# ProtonOnAStick.net
KiCad netlist of a schematic drawn in EAGLE
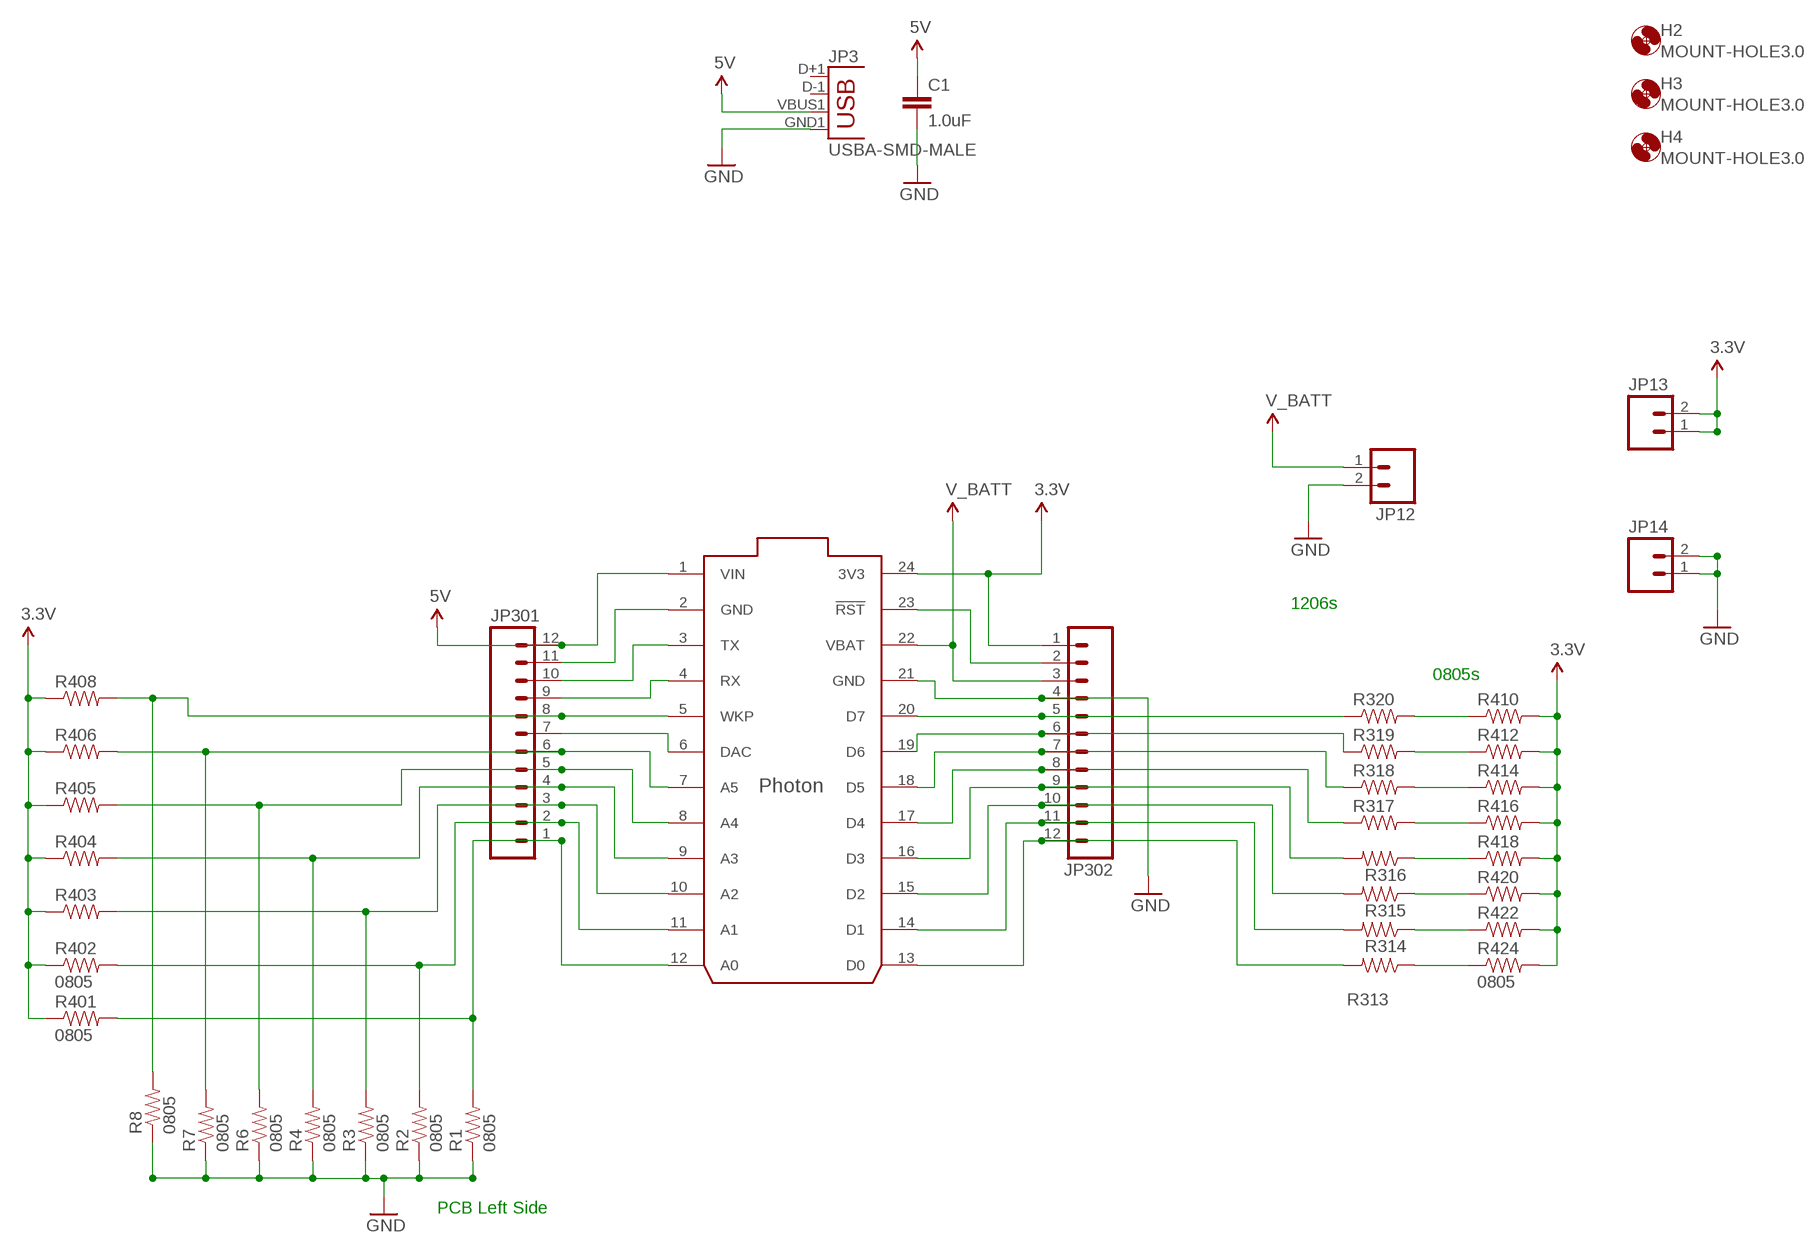
[diagram p0: schematic, sheet 1, part 1 of 2]
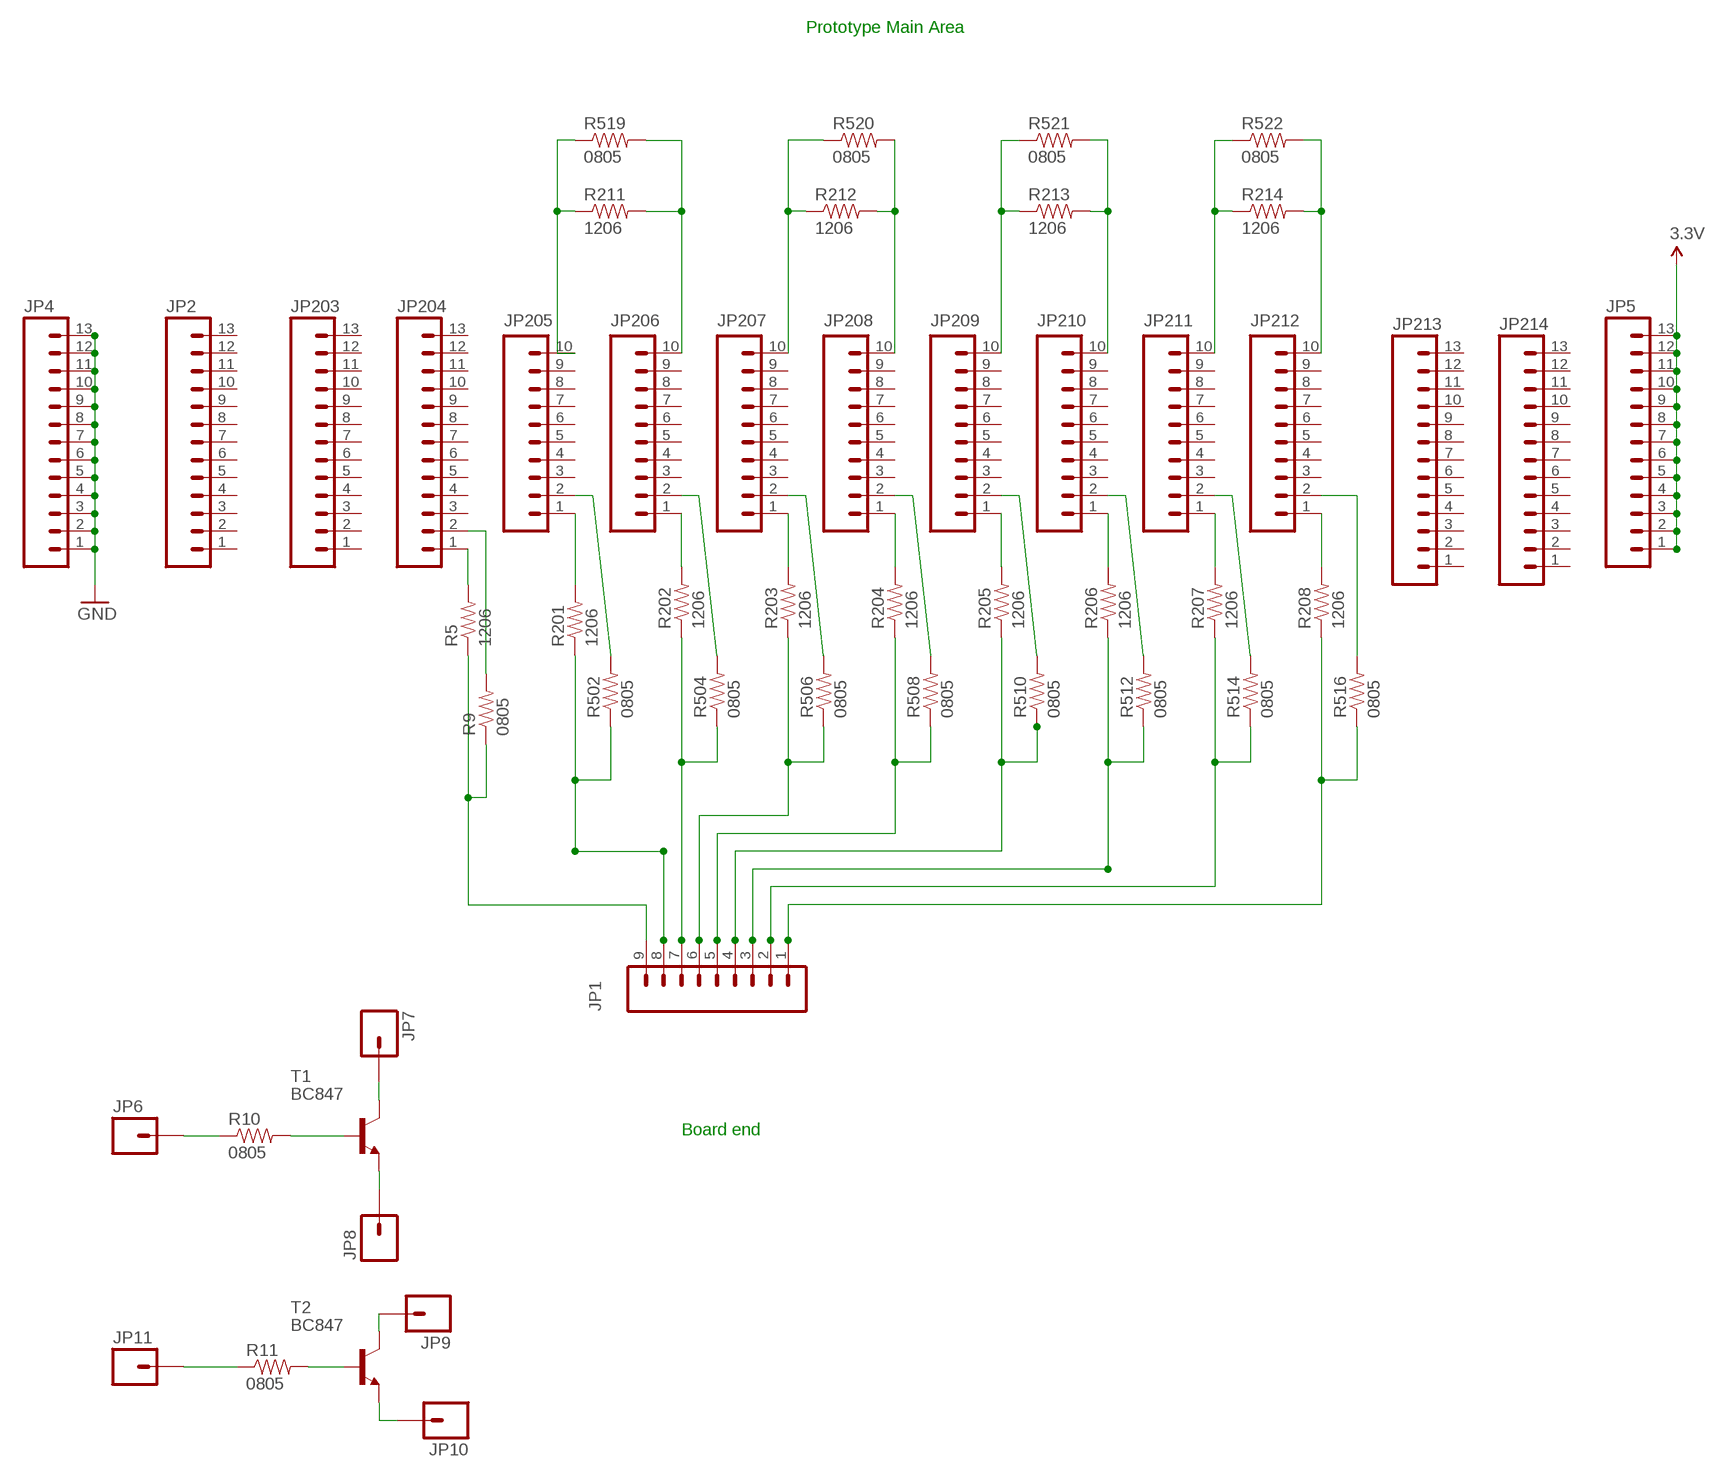
[diagram p1: schematic, sheet 1, part 2 of 2]

(export (version "E")
  (design (tool "Eeschema 10.0.6"))
  (components
    (comp (ref "C1")
      (value "1.0uF")
      (footprint "eagle-import:0805-CAP")
      (libsource (lib "eagle-import") (part "1.0UF-25V-+80/-20(0805){dblquote}"))
    )
    (comp (ref "H2")
      (value "MOUNT-HOLE3.0")
      (footprint "eagle-import:3,0")
      (libsource (lib "eagle-import") (part "MOUNT-HOLE3.0"))
    )
    (comp (ref "H3")
      (value "MOUNT-HOLE3.0")
      (footprint "eagle-import:3,0")
      (libsource (lib "eagle-import") (part "MOUNT-HOLE3.0"))
    )
    (comp (ref "H4")
      (value "MOUNT-HOLE3.0")
      (footprint "eagle-import:3,0")
      (libsource (lib "eagle-import") (part "MOUNT-HOLE3.0"))
    )
    (comp (ref "IC1")
      (value "PHOTON_WITH_HEADERS")
      (footprint "eagle-import:PHOTON")
      (libsource (lib "eagle-import") (part "PHOTON_WITH_HEADERS"))
    )
    (comp (ref "JP1")
      (value "M09")
      (footprint "eagle-import:1X09")
      (libsource (lib "eagle-import") (part "M09"))
    )
    (comp (ref "JP2")
      (value "M13")
      (footprint "eagle-import:1X13")
      (libsource (lib "eagle-import") (part "M13"))
    )
    (comp (ref "JP3")
      (value "USBA-SMD-MALE")
      (footprint "eagle-import:USB-A-SMT-MALE")
      (libsource (lib "eagle-import") (part "USBA-SMD-MALE"))
    )
    (comp (ref "JP4")
      (value "M13")
      (footprint "eagle-import:1X13")
      (libsource (lib "eagle-import") (part "M13"))
    )
    (comp (ref "JP5")
      (value "M13")
      (footprint "eagle-import:1X13")
      (libsource (lib "eagle-import") (part "M13"))
    )
    (comp (ref "JP6")
      (value "M01PTH")
      (footprint "eagle-import:1X01")
      (libsource (lib "eagle-import") (part "M01PTH"))
    )
    (comp (ref "JP7")
      (value "M01PTH")
      (footprint "eagle-import:1X01")
      (libsource (lib "eagle-import") (part "M01PTH"))
    )
    (comp (ref "JP8")
      (value "M01PTH")
      (footprint "eagle-import:1X01")
      (libsource (lib "eagle-import") (part "M01PTH"))
    )
    (comp (ref "JP9")
      (value "M01PTH")
      (footprint "eagle-import:1X01")
      (libsource (lib "eagle-import") (part "M01PTH"))
    )
    (comp (ref "JP10")
      (value "M01PTH")
      (footprint "eagle-import:1X01")
      (libsource (lib "eagle-import") (part "M01PTH"))
    )
    (comp (ref "JP11")
      (value "M01PTH")
      (footprint "eagle-import:1X01")
      (libsource (lib "eagle-import") (part "M01PTH"))
    )
    (comp (ref "JP12")
      (value "M02JST-PTH-2")
      (footprint "eagle-import:JST-2-PTH")
      (libsource (lib "eagle-import") (part "M02JST-PTH-2"))
    )
    (comp (ref "JP13")
      (value "M02PTH")
      (footprint "eagle-import:1X02")
      (libsource (lib "eagle-import") (part "M02PTH"))
    )
    (comp (ref "JP14")
      (value "M02PTH")
      (footprint "eagle-import:1X02")
      (libsource (lib "eagle-import") (part "M02PTH"))
    )
    (comp (ref "JP203")
      (value "M13")
      (footprint "eagle-import:1X13")
      (libsource (lib "eagle-import") (part "M13"))
    )
    (comp (ref "JP204")
      (value "M13")
      (footprint "eagle-import:1X13")
      (libsource (lib "eagle-import") (part "M13"))
    )
    (comp (ref "JP205")
      (value "M10SILK_FEMALE_PTH")
      (footprint "eagle-import:1X10")
      (libsource (lib "eagle-import") (part "M10SILK_FEMALE_PTH"))
    )
    (comp (ref "JP206")
      (value "M10SILK_FEMALE_PTH")
      (footprint "eagle-import:1X10")
      (libsource (lib "eagle-import") (part "M10SILK_FEMALE_PTH"))
    )
    (comp (ref "JP207")
      (value "M10SILK_FEMALE_PTH")
      (footprint "eagle-import:1X10")
      (libsource (lib "eagle-import") (part "M10SILK_FEMALE_PTH"))
    )
    (comp (ref "JP208")
      (value "M10SILK_FEMALE_PTH")
      (footprint "eagle-import:1X10")
      (libsource (lib "eagle-import") (part "M10SILK_FEMALE_PTH"))
    )
    (comp (ref "JP209")
      (value "M10SILK_FEMALE_PTH")
      (footprint "eagle-import:1X10")
      (libsource (lib "eagle-import") (part "M10SILK_FEMALE_PTH"))
    )
    (comp (ref "JP210")
      (value "M10SILK_FEMALE_PTH")
      (footprint "eagle-import:1X10")
      (libsource (lib "eagle-import") (part "M10SILK_FEMALE_PTH"))
    )
    (comp (ref "JP211")
      (value "M10SILK_FEMALE_PTH")
      (footprint "eagle-import:1X10")
      (libsource (lib "eagle-import") (part "M10SILK_FEMALE_PTH"))
    )
    (comp (ref "JP212")
      (value "M10SILK_FEMALE_PTH")
      (footprint "eagle-import:1X10")
      (libsource (lib "eagle-import") (part "M10SILK_FEMALE_PTH"))
    )
    (comp (ref "JP213")
      (value "M13")
      (footprint "eagle-import:1X13")
      (libsource (lib "eagle-import") (part "M13"))
    )
    (comp (ref "JP214")
      (value "M13")
      (footprint "eagle-import:1X13")
      (libsource (lib "eagle-import") (part "M13"))
    )
    (comp (ref "JP301")
      (value "M12PTH")
      (footprint "eagle-import:1X12")
      (libsource (lib "eagle-import") (part "M12PTH"))
    )
    (comp (ref "JP302")
      (value "M12PTH")
      (footprint "eagle-import:1X12")
      (libsource (lib "eagle-import") (part "M12PTH"))
    )
    (comp (ref "R1")
      (value "0805")
      (footprint "eagle-import:0805")
      (libsource (lib "eagle-import") (part "RESISTOR0805-RES"))
    )
    (comp (ref "R2")
      (value "0805")
      (footprint "eagle-import:0805")
      (libsource (lib "eagle-import") (part "RESISTOR0805-RES"))
    )
    (comp (ref "R3")
      (value "0805")
      (footprint "eagle-import:0805")
      (libsource (lib "eagle-import") (part "RESISTOR0805-RES"))
    )
    (comp (ref "R4")
      (value "0805")
      (footprint "eagle-import:0805")
      (libsource (lib "eagle-import") (part "RESISTOR0805-RES"))
    )
    (comp (ref "R5")
      (value "1206")
      (footprint "eagle-import:1206")
      (libsource (lib "eagle-import") (part "RESISTOR1206"))
    )
    (comp (ref "R6")
      (value "0805")
      (footprint "eagle-import:0805")
      (libsource (lib "eagle-import") (part "RESISTOR0805-RES"))
    )
    (comp (ref "R7")
      (value "0805")
      (footprint "eagle-import:0805")
      (libsource (lib "eagle-import") (part "RESISTOR0805-RES"))
    )
    (comp (ref "R8")
      (value "0805")
      (footprint "eagle-import:0805")
      (libsource (lib "eagle-import") (part "RESISTOR0805-RES"))
    )
    (comp (ref "R9")
      (value "0805")
      (footprint "eagle-import:0805")
      (libsource (lib "eagle-import") (part "RESISTOR0805-RES"))
    )
    (comp (ref "R10")
      (value "0805")
      (footprint "eagle-import:0805")
      (libsource (lib "eagle-import") (part "RESISTOR0805-RES"))
    )
    (comp (ref "R11")
      (value "0805")
      (footprint "eagle-import:0805")
      (libsource (lib "eagle-import") (part "RESISTOR0805-RES"))
    )
    (comp (ref "R201")
      (value "1206")
      (footprint "eagle-import:1206")
      (libsource (lib "eagle-import") (part "RESISTOR1206"))
    )
    (comp (ref "R202")
      (value "1206")
      (footprint "eagle-import:1206")
      (libsource (lib "eagle-import") (part "RESISTOR1206"))
    )
    (comp (ref "R203")
      (value "1206")
      (footprint "eagle-import:1206")
      (libsource (lib "eagle-import") (part "RESISTOR1206"))
    )
    (comp (ref "R204")
      (value "1206")
      (footprint "eagle-import:1206")
      (libsource (lib "eagle-import") (part "RESISTOR1206"))
    )
    (comp (ref "R205")
      (value "1206")
      (footprint "eagle-import:1206")
      (libsource (lib "eagle-import") (part "RESISTOR1206"))
    )
    (comp (ref "R206")
      (value "1206")
      (footprint "eagle-import:1206")
      (libsource (lib "eagle-import") (part "RESISTOR1206"))
    )
    (comp (ref "R207")
      (value "1206")
      (footprint "eagle-import:1206")
      (libsource (lib "eagle-import") (part "RESISTOR1206"))
    )
    (comp (ref "R208")
      (value "1206")
      (footprint "eagle-import:1206")
      (libsource (lib "eagle-import") (part "RESISTOR1206"))
    )
    (comp (ref "R211")
      (value "1206")
      (footprint "eagle-import:1206")
      (libsource (lib "eagle-import") (part "RESISTOR1206"))
    )
    (comp (ref "R212")
      (value "1206")
      (footprint "eagle-import:1206")
      (libsource (lib "eagle-import") (part "RESISTOR1206"))
    )
    (comp (ref "R213")
      (value "1206")
      (footprint "eagle-import:1206")
      (libsource (lib "eagle-import") (part "RESISTOR1206"))
    )
    (comp (ref "R214")
      (value "1206")
      (footprint "eagle-import:1206")
      (libsource (lib "eagle-import") (part "RESISTOR1206"))
    )
    (comp (ref "R313")
      (value "1206")
      (footprint "eagle-import:1206")
      (libsource (lib "eagle-import") (part "RESISTOR1206"))
    )
    (comp (ref "R314")
      (value "1206")
      (footprint "eagle-import:1206")
      (libsource (lib "eagle-import") (part "RESISTOR1206"))
    )
    (comp (ref "R315")
      (value "1206")
      (footprint "eagle-import:1206")
      (libsource (lib "eagle-import") (part "RESISTOR1206"))
    )
    (comp (ref "R316")
      (value "1206")
      (footprint "eagle-import:1206")
      (libsource (lib "eagle-import") (part "RESISTOR1206"))
    )
    (comp (ref "R317")
      (value "1206")
      (footprint "eagle-import:1206")
      (libsource (lib "eagle-import") (part "RESISTOR1206"))
    )
    (comp (ref "R318")
      (value "1206")
      (footprint "eagle-import:1206")
      (libsource (lib "eagle-import") (part "RESISTOR1206"))
    )
    (comp (ref "R319")
      (value "1206")
      (footprint "eagle-import:1206")
      (libsource (lib "eagle-import") (part "RESISTOR1206"))
    )
    (comp (ref "R320")
      (value "1206")
      (footprint "eagle-import:1206")
      (libsource (lib "eagle-import") (part "RESISTOR1206"))
    )
    (comp (ref "R401")
      (value "0805")
      (footprint "eagle-import:0805")
      (libsource (lib "eagle-import") (part "RESISTOR0805-RES"))
    )
    (comp (ref "R402")
      (value "0805")
      (footprint "eagle-import:0805")
      (libsource (lib "eagle-import") (part "RESISTOR0805-RES"))
    )
    (comp (ref "R403")
      (value "0805")
      (footprint "eagle-import:0805")
      (libsource (lib "eagle-import") (part "RESISTOR0805-RES"))
    )
    (comp (ref "R404")
      (value "0805")
      (footprint "eagle-import:0805")
      (libsource (lib "eagle-import") (part "RESISTOR0805-RES"))
    )
    (comp (ref "R405")
      (value "0805")
      (footprint "eagle-import:0805")
      (libsource (lib "eagle-import") (part "RESISTOR0805-RES"))
    )
    (comp (ref "R406")
      (value "0805")
      (footprint "eagle-import:0805")
      (libsource (lib "eagle-import") (part "RESISTOR0805-RES"))
    )
    (comp (ref "R408")
      (value "0805")
      (footprint "eagle-import:0805")
      (libsource (lib "eagle-import") (part "RESISTOR0805-RES"))
    )
    (comp (ref "R410")
      (value "0805")
      (footprint "eagle-import:0805")
      (libsource (lib "eagle-import") (part "RESISTOR0805-RES"))
    )
    (comp (ref "R412")
      (value "0805")
      (footprint "eagle-import:0805")
      (libsource (lib "eagle-import") (part "RESISTOR0805-RES"))
    )
    (comp (ref "R414")
      (value "0805")
      (footprint "eagle-import:0805")
      (libsource (lib "eagle-import") (part "RESISTOR0805-RES"))
    )
    (comp (ref "R416")
      (value "0805")
      (footprint "eagle-import:0805")
      (libsource (lib "eagle-import") (part "RESISTOR0805-RES"))
    )
    (comp (ref "R418")
      (value "0805")
      (footprint "eagle-import:0805")
      (libsource (lib "eagle-import") (part "RESISTOR0805-RES"))
    )
    (comp (ref "R420")
      (value "0805")
      (footprint "eagle-import:0805")
      (libsource (lib "eagle-import") (part "RESISTOR0805-RES"))
    )
    (comp (ref "R422")
      (value "0805")
      (footprint "eagle-import:0805")
      (libsource (lib "eagle-import") (part "RESISTOR0805-RES"))
    )
    (comp (ref "R424")
      (value "0805")
      (footprint "eagle-import:0805")
      (libsource (lib "eagle-import") (part "RESISTOR0805-RES"))
    )
    (comp (ref "R502")
      (value "0805")
      (footprint "eagle-import:0805")
      (libsource (lib "eagle-import") (part "RESISTOR0805-RES"))
    )
    (comp (ref "R504")
      (value "0805")
      (footprint "eagle-import:0805")
      (libsource (lib "eagle-import") (part "RESISTOR0805-RES"))
    )
    (comp (ref "R506")
      (value "0805")
      (footprint "eagle-import:0805")
      (libsource (lib "eagle-import") (part "RESISTOR0805-RES"))
    )
    (comp (ref "R508")
      (value "0805")
      (footprint "eagle-import:0805")
      (libsource (lib "eagle-import") (part "RESISTOR0805-RES"))
    )
    (comp (ref "R510")
      (value "0805")
      (footprint "eagle-import:0805")
      (libsource (lib "eagle-import") (part "RESISTOR0805-RES"))
    )
    (comp (ref "R512")
      (value "0805")
      (footprint "eagle-import:0805")
      (libsource (lib "eagle-import") (part "RESISTOR0805-RES"))
    )
    (comp (ref "R514")
      (value "0805")
      (footprint "eagle-import:0805")
      (libsource (lib "eagle-import") (part "RESISTOR0805-RES"))
    )
    (comp (ref "R516")
      (value "0805")
      (footprint "eagle-import:0805")
      (libsource (lib "eagle-import") (part "RESISTOR0805-RES"))
    )
    (comp (ref "R519")
      (value "0805")
      (footprint "eagle-import:0805")
      (libsource (lib "eagle-import") (part "RESISTOR0805-RES"))
    )
    (comp (ref "R520")
      (value "0805")
      (footprint "eagle-import:0805")
      (libsource (lib "eagle-import") (part "RESISTOR0805-RES"))
    )
    (comp (ref "R521")
      (value "0805")
      (footprint "eagle-import:0805")
      (libsource (lib "eagle-import") (part "RESISTOR0805-RES"))
    )
    (comp (ref "R522")
      (value "0805")
      (footprint "eagle-import:0805")
      (libsource (lib "eagle-import") (part "RESISTOR0805-RES"))
    )
    (comp (ref "T1")
      (value "BC847")
      (footprint "eagle-import:SOT23")
      (libsource (lib "eagle-import") (part "BC847"))
    )
    (comp (ref "T2")
      (value "BC847")
      (footprint "eagle-import:SOT23")
      (libsource (lib "eagle-import") (part "BC847"))
    )
  )
  (nets
    (net (code "1") (name "3.3V") (class "Default")
      (node (ref "IC1") (pin "24") (pinfunction "3V3_24") (pintype "power_in"))
      (node (ref "JP13") (pin "1") (pinfunction "1_1") (pintype "passive"))
      (node (ref "JP13") (pin "2") (pinfunction "2_2") (pintype "passive"))
      (node (ref "JP302") (pin "1") (pinfunction "1_1") (pintype "passive"))
      (node (ref "JP5") (pin "1") (pinfunction "1_1") (pintype "passive"))
      (node (ref "JP5") (pin "10") (pinfunction "10_10") (pintype "passive"))
      (node (ref "JP5") (pin "11") (pinfunction "11_11") (pintype "passive"))
      (node (ref "JP5") (pin "12") (pinfunction "12_12") (pintype "passive"))
      (node (ref "JP5") (pin "13") (pinfunction "13_13") (pintype "passive"))
      (node (ref "JP5") (pin "2") (pinfunction "2_2") (pintype "passive"))
      (node (ref "JP5") (pin "3") (pinfunction "3_3") (pintype "passive"))
      (node (ref "JP5") (pin "4") (pinfunction "4_4") (pintype "passive"))
      (node (ref "JP5") (pin "5") (pinfunction "5_5") (pintype "passive"))
      (node (ref "JP5") (pin "6") (pinfunction "6_6") (pintype "passive"))
      (node (ref "JP5") (pin "7") (pinfunction "7_7") (pintype "passive"))
      (node (ref "JP5") (pin "8") (pinfunction "8_8") (pintype "passive"))
      (node (ref "JP5") (pin "9") (pinfunction "9_9") (pintype "passive"))
      (node (ref "R401") (pin "1") (pinfunction "1_1") (pintype "passive"))
      (node (ref "R402") (pin "1") (pinfunction "1_1") (pintype "passive"))
      (node (ref "R403") (pin "1") (pinfunction "1_1") (pintype "passive"))
      (node (ref "R404") (pin "1") (pinfunction "1_1") (pintype "passive"))
      (node (ref "R405") (pin "1") (pinfunction "1_1") (pintype "passive"))
      (node (ref "R406") (pin "1") (pinfunction "1_1") (pintype "passive"))
      (node (ref "R408") (pin "1") (pinfunction "1_1") (pintype "passive"))
      (node (ref "R410") (pin "2") (pinfunction "2_2") (pintype "passive"))
      (node (ref "R412") (pin "2") (pinfunction "2_2") (pintype "passive"))
      (node (ref "R414") (pin "2") (pinfunction "2_2") (pintype "passive"))
      (node (ref "R416") (pin "2") (pinfunction "2_2") (pintype "passive"))
      (node (ref "R418") (pin "2") (pinfunction "2_2") (pintype "passive"))
      (node (ref "R420") (pin "2") (pinfunction "2_2") (pintype "passive"))
      (node (ref "R422") (pin "2") (pinfunction "2_2") (pintype "passive"))
      (node (ref "R424") (pin "2") (pinfunction "2_2") (pintype "passive"))
    )
    (net (code "2") (name "5V") (class "Default")
      (node (ref "C1") (pin "1") (pinfunction "1_1") (pintype "passive"))
      (node (ref "IC1") (pin "1") (pinfunction "VIN_1") (pintype "power_in"))
      (node (ref "JP3") (pin "VBUS1") (pinfunction "VBUS_VBUS1") (pintype "bidirectional"))
      (node (ref "JP301") (pin "12") (pinfunction "12_12") (pintype "passive"))
    )
    (net (code "3") (name "GND") (class "Default")
      (node (ref "C1") (pin "2") (pinfunction "2_2") (pintype "passive"))
      (node (ref "IC1") (pin "2") (pinfunction "GND_2") (pintype "power_in"))
      (node (ref "IC1") (pin "21") (pinfunction "GND_21") (pintype "power_in"))
      (node (ref "JP12") (pin "2") (pinfunction "2_2") (pintype "passive"))
      (node (ref "JP14") (pin "1") (pinfunction "1_1") (pintype "passive"))
      (node (ref "JP14") (pin "2") (pinfunction "2_2") (pintype "passive"))
      (node (ref "JP3") (pin "GND1") (pinfunction "GND_GND1") (pintype "bidirectional"))
      (node (ref "JP301") (pin "11") (pinfunction "11_11") (pintype "passive"))
      (node (ref "JP302") (pin "4") (pinfunction "4_4") (pintype "passive"))
      (node (ref "JP4") (pin "1") (pinfunction "1_1") (pintype "passive"))
      (node (ref "JP4") (pin "10") (pinfunction "10_10") (pintype "passive"))
      (node (ref "JP4") (pin "11") (pinfunction "11_11") (pintype "passive"))
      (node (ref "JP4") (pin "12") (pinfunction "12_12") (pintype "passive"))
      (node (ref "JP4") (pin "13") (pinfunction "13_13") (pintype "passive"))
      (node (ref "JP4") (pin "2") (pinfunction "2_2") (pintype "passive"))
      (node (ref "JP4") (pin "3") (pinfunction "3_3") (pintype "passive"))
      (node (ref "JP4") (pin "4") (pinfunction "4_4") (pintype "passive"))
      (node (ref "JP4") (pin "5") (pinfunction "5_5") (pintype "passive"))
      (node (ref "JP4") (pin "6") (pinfunction "6_6") (pintype "passive"))
      (node (ref "JP4") (pin "7") (pinfunction "7_7") (pintype "passive"))
      (node (ref "JP4") (pin "8") (pinfunction "8_8") (pintype "passive"))
      (node (ref "JP4") (pin "9") (pinfunction "9_9") (pintype "passive"))
      (node (ref "R1") (pin "1") (pinfunction "1_1") (pintype "passive"))
      (node (ref "R2") (pin "1") (pinfunction "1_1") (pintype "passive"))
      (node (ref "R3") (pin "1") (pinfunction "1_1") (pintype "passive"))
      (node (ref "R4") (pin "1") (pinfunction "1_1") (pintype "passive"))
      (node (ref "R6") (pin "1") (pinfunction "1_1") (pintype "passive"))
      (node (ref "R7") (pin "1") (pinfunction "1_1") (pintype "passive"))
      (node (ref "R8") (pin "1") (pinfunction "1_1") (pintype "passive"))
    )
    (net (code "4") (name "Net-(IC1-A0)") (class "Default")
      (node (ref "IC1") (pin "12") (pinfunction "A0_12") (pintype "bidirectional"))
      (node (ref "JP301") (pin "1") (pinfunction "1_1") (pintype "passive"))
      (node (ref "R1") (pin "2") (pinfunction "2_2") (pintype "passive"))
      (node (ref "R401") (pin "2") (pinfunction "2_2") (pintype "passive"))
    )
    (net (code "5") (name "Net-(IC1-A1)") (class "Default")
      (node (ref "IC1") (pin "11") (pinfunction "A1_11") (pintype "bidirectional"))
      (node (ref "JP301") (pin "2") (pinfunction "2_2") (pintype "passive"))
      (node (ref "R2") (pin "2") (pinfunction "2_2") (pintype "passive"))
      (node (ref "R402") (pin "2") (pinfunction "2_2") (pintype "passive"))
    )
    (net (code "6") (name "Net-(IC1-A2)") (class "Default")
      (node (ref "IC1") (pin "10") (pinfunction "A2_10") (pintype "bidirectional"))
      (node (ref "JP301") (pin "3") (pinfunction "3_3") (pintype "passive"))
      (node (ref "R3") (pin "2") (pinfunction "2_2") (pintype "passive"))
      (node (ref "R403") (pin "2") (pinfunction "2_2") (pintype "passive"))
    )
    (net (code "7") (name "Net-(IC1-A3)") (class "Default")
      (node (ref "IC1") (pin "9") (pinfunction "A3_9") (pintype "bidirectional"))
      (node (ref "JP301") (pin "4") (pinfunction "4_4") (pintype "passive"))
      (node (ref "R4") (pin "2") (pinfunction "2_2") (pintype "passive"))
      (node (ref "R404") (pin "2") (pinfunction "2_2") (pintype "passive"))
    )
    (net (code "8") (name "Net-(IC1-A4)") (class "Default")
      (node (ref "IC1") (pin "8") (pinfunction "A4_8") (pintype "bidirectional"))
      (node (ref "JP301") (pin "5") (pinfunction "5_5") (pintype "passive"))
      (node (ref "R405") (pin "2") (pinfunction "2_2") (pintype "passive"))
      (node (ref "R6") (pin "2") (pinfunction "2_2") (pintype "passive"))
    )
    (net (code "9") (name "Net-(IC1-A5)") (class "Default")
      (node (ref "IC1") (pin "7") (pinfunction "A5_7") (pintype "bidirectional"))
      (node (ref "JP301") (pin "6") (pinfunction "6_6") (pintype "passive"))
      (node (ref "R406") (pin "2") (pinfunction "2_2") (pintype "passive"))
      (node (ref "R7") (pin "2") (pinfunction "2_2") (pintype "passive"))
    )
    (net (code "10") (name "Net-(IC1-D0)") (class "Default")
      (node (ref "IC1") (pin "13") (pinfunction "D0_13") (pintype "bidirectional"))
      (node (ref "JP302") (pin "12") (pinfunction "12_12") (pintype "passive"))
      (node (ref "R313") (pin "2") (pinfunction "2_2") (pintype "passive"))
    )
    (net (code "11") (name "Net-(IC1-D1)") (class "Default")
      (node (ref "IC1") (pin "14") (pinfunction "D1_14") (pintype "bidirectional"))
      (node (ref "JP302") (pin "11") (pinfunction "11_11") (pintype "passive"))
      (node (ref "R314") (pin "2") (pinfunction "2_2") (pintype "passive"))
    )
    (net (code "12") (name "Net-(IC1-D2)") (class "Default")
      (node (ref "IC1") (pin "15") (pinfunction "D2_15") (pintype "bidirectional"))
      (node (ref "JP302") (pin "10") (pinfunction "10_10") (pintype "passive"))
      (node (ref "R315") (pin "2") (pinfunction "2_2") (pintype "passive"))
    )
    (net (code "13") (name "Net-(IC1-D3)") (class "Default")
      (node (ref "IC1") (pin "16") (pinfunction "D3_16") (pintype "bidirectional"))
      (node (ref "JP302") (pin "9") (pinfunction "9_9") (pintype "passive"))
      (node (ref "R316") (pin "2") (pinfunction "2_2") (pintype "passive"))
    )
    (net (code "14") (name "Net-(IC1-D4)") (class "Default")
      (node (ref "IC1") (pin "17") (pinfunction "D4_17") (pintype "bidirectional"))
      (node (ref "JP302") (pin "8") (pinfunction "8_8") (pintype "passive"))
      (node (ref "R317") (pin "1") (pinfunction "1_1") (pintype "passive"))
    )
    (net (code "15") (name "Net-(IC1-D5)") (class "Default")
      (node (ref "IC1") (pin "18") (pinfunction "D5_18") (pintype "bidirectional"))
      (node (ref "JP302") (pin "7") (pinfunction "7_7") (pintype "passive"))
      (node (ref "R318") (pin "1") (pinfunction "1_1") (pintype "passive"))
    )
    (net (code "16") (name "Net-(IC1-D6)") (class "Default")
      (node (ref "IC1") (pin "19") (pinfunction "D6_19") (pintype "bidirectional"))
      (node (ref "JP302") (pin "6") (pinfunction "6_6") (pintype "passive"))
      (node (ref "R319") (pin "1") (pinfunction "1_1") (pintype "passive"))
    )
    (net (code "17") (name "Net-(IC1-D7)") (class "Default")
      (node (ref "IC1") (pin "20") (pinfunction "D7_20") (pintype "bidirectional"))
      (node (ref "JP302") (pin "5") (pinfunction "5_5") (pintype "passive"))
      (node (ref "R320") (pin "1") (pinfunction "1_1") (pintype "passive"))
    )
    (net (code "18") (name "Net-(IC1-DAC)") (class "Default")
      (node (ref "IC1") (pin "6") (pinfunction "DAC_6") (pintype "bidirectional"))
      (node (ref "JP301") (pin "7") (pinfunction "7_7") (pintype "passive"))
    )
    (net (code "19") (name "Net-(IC1-RX)") (class "Default")
      (node (ref "IC1") (pin "4") (pinfunction "RX_4") (pintype "bidirectional"))
      (node (ref "JP301") (pin "9") (pinfunction "9_9") (pintype "passive"))
    )
    (net (code "20") (name "Net-(IC1-TX)") (class "Default")
      (node (ref "IC1") (pin "3") (pinfunction "TX_3") (pintype "bidirectional"))
      (node (ref "JP301") (pin "10") (pinfunction "10_10") (pintype "passive"))
    )
    (net (code "21") (name "Net-(IC1-WKP)") (class "Default")
      (node (ref "IC1") (pin "5") (pinfunction "WKP_5") (pintype "bidirectional"))
      (node (ref "JP301") (pin "8") (pinfunction "8_8") (pintype "passive"))
      (node (ref "R408") (pin "2") (pinfunction "2_2") (pintype "passive"))
      (node (ref "R8") (pin "2") (pinfunction "2_2") (pintype "passive"))
    )
    (net (code "22") (name "Net-(IC1-~{RST})") (class "Default")
      (node (ref "IC1") (pin "23") (pinfunction "~{RST}_23") (pintype "bidirectional"))
      (node (ref "JP302") (pin "2") (pinfunction "2_2") (pintype "passive"))
    )
    (net (code "23") (name "Net-(JP1-Pad1)") (class "Default")
      (node (ref "JP1") (pin "1") (pinfunction "1_1") (pintype "passive"))
      (node (ref "R208") (pin "1") (pinfunction "1_1") (pintype "passive"))
      (node (ref "R516") (pin "1") (pinfunction "1_1") (pintype "passive"))
    )
    (net (code "24") (name "Net-(JP1-Pad2)") (class "Default")
      (node (ref "JP1") (pin "2") (pinfunction "2_2") (pintype "passive"))
      (node (ref "R207") (pin "1") (pinfunction "1_1") (pintype "passive"))
      (node (ref "R514") (pin "1") (pinfunction "1_1") (pintype "passive"))
    )
    (net (code "25") (name "Net-(JP1-Pad3)") (class "Default")
      (node (ref "JP1") (pin "3") (pinfunction "3_3") (pintype "passive"))
      (node (ref "R206") (pin "1") (pinfunction "1_1") (pintype "passive"))
      (node (ref "R512") (pin "1") (pinfunction "1_1") (pintype "passive"))
    )
    (net (code "26") (name "Net-(JP1-Pad4)") (class "Default")
      (node (ref "JP1") (pin "4") (pinfunction "4_4") (pintype "passive"))
      (node (ref "R205") (pin "1") (pinfunction "1_1") (pintype "passive"))
      (node (ref "R510") (pin "1") (pinfunction "1_1") (pintype "passive"))
    )
    (net (code "27") (name "Net-(JP1-Pad5)") (class "Default")
      (node (ref "JP1") (pin "5") (pinfunction "5_5") (pintype "passive"))
      (node (ref "R204") (pin "1") (pinfunction "1_1") (pintype "passive"))
      (node (ref "R508") (pin "1") (pinfunction "1_1") (pintype "passive"))
    )
    (net (code "28") (name "Net-(JP1-Pad6)") (class "Default")
      (node (ref "JP1") (pin "6") (pinfunction "6_6") (pintype "passive"))
      (node (ref "R203") (pin "1") (pinfunction "1_1") (pintype "passive"))
      (node (ref "R506") (pin "1") (pinfunction "1_1") (pintype "passive"))
    )
    (net (code "29") (name "Net-(JP1-Pad7)") (class "Default")
      (node (ref "JP1") (pin "7") (pinfunction "7_7") (pintype "passive"))
      (node (ref "R202") (pin "1") (pinfunction "1_1") (pintype "passive"))
      (node (ref "R504") (pin "1") (pinfunction "1_1") (pintype "passive"))
    )
    (net (code "30") (name "Net-(JP1-Pad8)") (class "Default")
      (node (ref "JP1") (pin "8") (pinfunction "8_8") (pintype "passive"))
      (node (ref "R201") (pin "1") (pinfunction "1_1") (pintype "passive"))
      (node (ref "R502") (pin "1") (pinfunction "1_1") (pintype "passive"))
    )
    (net (code "31") (name "Net-(JP1-Pad9)") (class "Default")
      (node (ref "JP1") (pin "9") (pinfunction "9_9") (pintype "passive"))
      (node (ref "R5") (pin "1") (pinfunction "1_1") (pintype "passive"))
      (node (ref "R9") (pin "1") (pinfunction "1_1") (pintype "passive"))
    )
    (net (code "32") (name "Net-(JP6-Pad1)") (class "Default")
      (node (ref "JP6") (pin "1") (pinfunction "1_1") (pintype "passive"))
      (node (ref "R10") (pin "1") (pinfunction "1_1") (pintype "passive"))
    )
    (net (code "33") (name "Net-(JP11-Pad1)") (class "Default")
      (node (ref "JP11") (pin "1") (pinfunction "1_1") (pintype "passive"))
      (node (ref "R11") (pin "1") (pinfunction "1_1") (pintype "passive"))
    )
    (net (code "34") (name "Net-(JP204-Pad1)") (class "Default")
      (node (ref "JP204") (pin "1") (pinfunction "1_1") (pintype "passive"))
      (node (ref "R5") (pin "2") (pinfunction "2_2") (pintype "passive"))
    )
    (net (code "35") (name "Net-(JP204-Pad2)") (class "Default")
      (node (ref "JP204") (pin "2") (pinfunction "2_2") (pintype "passive"))
      (node (ref "R9") (pin "2") (pinfunction "2_2") (pintype "passive"))
    )
    (net (code "36") (name "Net-(JP205-Pad1)") (class "Default")
      (node (ref "JP205") (pin "1") (pinfunction "1_1") (pintype "passive"))
      (node (ref "R201") (pin "2") (pinfunction "2_2") (pintype "passive"))
    )
    (net (code "37") (name "Net-(JP205-Pad2)") (class "Default")
      (node (ref "JP205") (pin "2") (pinfunction "2_2") (pintype "passive"))
      (node (ref "R502") (pin "2") (pinfunction "2_2") (pintype "passive"))
    )
    (net (code "38") (name "Net-(JP205-Pad10)") (class "Default")
      (node (ref "JP205") (pin "10") (pinfunction "10_10") (pintype "passive"))
      (node (ref "R211") (pin "1") (pinfunction "1_1") (pintype "passive"))
      (node (ref "R519") (pin "1") (pinfunction "1_1") (pintype "passive"))
    )
    (net (code "39") (name "Net-(JP206-Pad1)") (class "Default")
      (node (ref "JP206") (pin "1") (pinfunction "1_1") (pintype "passive"))
      (node (ref "R202") (pin "2") (pinfunction "2_2") (pintype "passive"))
    )
    (net (code "40") (name "Net-(JP206-Pad2)") (class "Default")
      (node (ref "JP206") (pin "2") (pinfunction "2_2") (pintype "passive"))
      (node (ref "R504") (pin "2") (pinfunction "2_2") (pintype "passive"))
    )
    (net (code "41") (name "Net-(JP206-Pad10)") (class "Default")
      (node (ref "JP206") (pin "10") (pinfunction "10_10") (pintype "passive"))
      (node (ref "R211") (pin "2") (pinfunction "2_2") (pintype "passive"))
      (node (ref "R519") (pin "2") (pinfunction "2_2") (pintype "passive"))
    )
    (net (code "42") (name "Net-(JP207-Pad1)") (class "Default")
      (node (ref "JP207") (pin "1") (pinfunction "1_1") (pintype "passive"))
      (node (ref "R203") (pin "2") (pinfunction "2_2") (pintype "passive"))
    )
    (net (code "43") (name "Net-(JP207-Pad2)") (class "Default")
      (node (ref "JP207") (pin "2") (pinfunction "2_2") (pintype "passive"))
      (node (ref "R506") (pin "2") (pinfunction "2_2") (pintype "passive"))
    )
    (net (code "44") (name "Net-(JP207-Pad10)") (class "Default")
      (node (ref "JP207") (pin "10") (pinfunction "10_10") (pintype "passive"))
      (node (ref "R212") (pin "1") (pinfunction "1_1") (pintype "passive"))
      (node (ref "R520") (pin "1") (pinfunction "1_1") (pintype "passive"))
    )
    (net (code "45") (name "Net-(JP208-Pad1)") (class "Default")
      (node (ref "JP208") (pin "1") (pinfunction "1_1") (pintype "passive"))
      (node (ref "R204") (pin "2") (pinfunction "2_2") (pintype "passive"))
    )
    (net (code "46") (name "Net-(JP208-Pad2)") (class "Default")
      (node (ref "JP208") (pin "2") (pinfunction "2_2") (pintype "passive"))
      (node (ref "R508") (pin "2") (pinfunction "2_2") (pintype "passive"))
    )
    (net (code "47") (name "Net-(JP208-Pad10)") (class "Default")
      (node (ref "JP208") (pin "10") (pinfunction "10_10") (pintype "passive"))
      (node (ref "R212") (pin "2") (pinfunction "2_2") (pintype "passive"))
      (node (ref "R520") (pin "2") (pinfunction "2_2") (pintype "passive"))
    )
    (net (code "48") (name "Net-(JP209-Pad1)") (class "Default")
      (node (ref "JP209") (pin "1") (pinfunction "1_1") (pintype "passive"))
      (node (ref "R205") (pin "2") (pinfunction "2_2") (pintype "passive"))
    )
    (net (code "49") (name "Net-(JP209-Pad2)") (class "Default")
      (node (ref "JP209") (pin "2") (pinfunction "2_2") (pintype "passive"))
      (node (ref "R510") (pin "2") (pinfunction "2_2") (pintype "passive"))
    )
    (net (code "50") (name "Net-(JP209-Pad10)") (class "Default")
      (node (ref "JP209") (pin "10") (pinfunction "10_10") (pintype "passive"))
      (node (ref "R213") (pin "1") (pinfunction "1_1") (pintype "passive"))
      (node (ref "R521") (pin "1") (pinfunction "1_1") (pintype "passive"))
    )
    (net (code "51") (name "Net-(JP210-Pad1)") (class "Default")
      (node (ref "JP210") (pin "1") (pinfunction "1_1") (pintype "passive"))
      (node (ref "R206") (pin "2") (pinfunction "2_2") (pintype "passive"))
    )
    (net (code "52") (name "Net-(JP210-Pad2)") (class "Default")
      (node (ref "JP210") (pin "2") (pinfunction "2_2") (pintype "passive"))
      (node (ref "R512") (pin "2") (pinfunction "2_2") (pintype "passive"))
    )
    (net (code "53") (name "Net-(JP210-Pad10)") (class "Default")
      (node (ref "JP210") (pin "10") (pinfunction "10_10") (pintype "passive"))
      (node (ref "R213") (pin "2") (pinfunction "2_2") (pintype "passive"))
      (node (ref "R521") (pin "2") (pinfunction "2_2") (pintype "passive"))
    )
    (net (code "54") (name "Net-(JP211-Pad1)") (class "Default")
      (node (ref "JP211") (pin "1") (pinfunction "1_1") (pintype "passive"))
      (node (ref "R207") (pin "2") (pinfunction "2_2") (pintype "passive"))
    )
    (net (code "55") (name "Net-(JP211-Pad2)") (class "Default")
      (node (ref "JP211") (pin "2") (pinfunction "2_2") (pintype "passive"))
      (node (ref "R514") (pin "2") (pinfunction "2_2") (pintype "passive"))
    )
    (net (code "56") (name "Net-(JP211-Pad10)") (class "Default")
      (node (ref "JP211") (pin "10") (pinfunction "10_10") (pintype "passive"))
      (node (ref "R214") (pin "1") (pinfunction "1_1") (pintype "passive"))
      (node (ref "R522") (pin "1") (pinfunction "1_1") (pintype "passive"))
    )
    (net (code "57") (name "Net-(JP212-Pad1)") (class "Default")
      (node (ref "JP212") (pin "1") (pinfunction "1_1") (pintype "passive"))
      (node (ref "R208") (pin "2") (pinfunction "2_2") (pintype "passive"))
    )
    (net (code "58") (name "Net-(JP212-Pad2)") (class "Default")
      (node (ref "JP212") (pin "2") (pinfunction "2_2") (pintype "passive"))
      (node (ref "R516") (pin "2") (pinfunction "2_2") (pintype "passive"))
    )
    (net (code "59") (name "Net-(JP212-Pad10)") (class "Default")
      (node (ref "JP212") (pin "10") (pinfunction "10_10") (pintype "passive"))
      (node (ref "R214") (pin "2") (pinfunction "2_2") (pintype "passive"))
      (node (ref "R522") (pin "2") (pinfunction "2_2") (pintype "passive"))
    )
    (net (code "60") (name "Net-(R313-Pad1)") (class "Default")
      (node (ref "R313") (pin "1") (pinfunction "1_1") (pintype "passive"))
      (node (ref "R424") (pin "1") (pinfunction "1_1") (pintype "passive"))
    )
    (net (code "61") (name "Net-(R314-Pad1)") (class "Default")
      (node (ref "R314") (pin "1") (pinfunction "1_1") (pintype "passive"))
      (node (ref "R422") (pin "1") (pinfunction "1_1") (pintype "passive"))
    )
    (net (code "62") (name "Net-(R315-Pad1)") (class "Default")
      (node (ref "R315") (pin "1") (pinfunction "1_1") (pintype "passive"))
      (node (ref "R420") (pin "1") (pinfunction "1_1") (pintype "passive"))
    )
    (net (code "63") (name "Net-(R316-Pad1)") (class "Default")
      (node (ref "R316") (pin "1") (pinfunction "1_1") (pintype "passive"))
      (node (ref "R418") (pin "1") (pinfunction "1_1") (pintype "passive"))
    )
    (net (code "64") (name "Net-(R317-Pad2)") (class "Default")
      (node (ref "R317") (pin "2") (pinfunction "2_2") (pintype "passive"))
      (node (ref "R416") (pin "1") (pinfunction "1_1") (pintype "passive"))
    )
    (net (code "65") (name "Net-(R318-Pad2)") (class "Default")
      (node (ref "R318") (pin "2") (pinfunction "2_2") (pintype "passive"))
      (node (ref "R414") (pin "1") (pinfunction "1_1") (pintype "passive"))
    )
    (net (code "66") (name "Net-(R319-Pad2)") (class "Default")
      (node (ref "R319") (pin "2") (pinfunction "2_2") (pintype "passive"))
      (node (ref "R412") (pin "1") (pinfunction "1_1") (pintype "passive"))
    )
    (net (code "67") (name "Net-(R320-Pad2)") (class "Default")
      (node (ref "R320") (pin "2") (pinfunction "2_2") (pintype "passive"))
      (node (ref "R410") (pin "1") (pinfunction "1_1") (pintype "passive"))
    )
    (net (code "68") (name "Net-(T1-B)") (class "Default")
      (node (ref "R10") (pin "2") (pinfunction "2_2") (pintype "passive"))
      (node (ref "T1") (pin "1") (pinfunction "B_1") (pintype "passive"))
    )
    (net (code "69") (name "Net-(T1-C)") (class "Default")
      (node (ref "JP7") (pin "1") (pinfunction "1_1") (pintype "passive"))
      (node (ref "T1") (pin "3") (pinfunction "C_3") (pintype "passive"))
    )
    (net (code "70") (name "Net-(T1-E)") (class "Default")
      (node (ref "JP8") (pin "1") (pinfunction "1_1") (pintype "passive"))
      (node (ref "T1") (pin "2") (pinfunction "E_2") (pintype "passive"))
    )
    (net (code "71") (name "Net-(T2-B)") (class "Default")
      (node (ref "R11") (pin "2") (pinfunction "2_2") (pintype "passive"))
      (node (ref "T2") (pin "1") (pinfunction "B_1") (pintype "passive"))
    )
    (net (code "72") (name "Net-(T2-C)") (class "Default")
      (node (ref "JP9") (pin "1") (pinfunction "1_1") (pintype "passive"))
      (node (ref "T2") (pin "3") (pinfunction "C_3") (pintype "passive"))
    )
    (net (code "73") (name "Net-(T2-E)") (class "Default")
      (node (ref "JP10") (pin "1") (pinfunction "1_1") (pintype "passive"))
      (node (ref "T2") (pin "2") (pinfunction "E_2") (pintype "passive"))
    )
    (net (code "74") (name "V_BATT") (class "Default")
      (node (ref "IC1") (pin "22") (pinfunction "VBAT_22") (pintype "power_in"))
      (node (ref "JP12") (pin "1") (pinfunction "1_1") (pintype "passive"))
      (node (ref "JP302") (pin "3") (pinfunction "3_3") (pintype "passive"))
    )
    (net (code "75") (name "unconnected-(JP2-Pad1)") (class "Default")
      (node (ref "JP2") (pin "1") (pinfunction "1_1") (pintype "passive"))
    )
    (net (code "76") (name "unconnected-(JP2-Pad2)") (class "Default")
      (node (ref "JP2") (pin "2") (pinfunction "2_2") (pintype "passive"))
    )
    (net (code "77") (name "unconnected-(JP2-Pad3)") (class "Default")
      (node (ref "JP2") (pin "3") (pinfunction "3_3") (pintype "passive"))
    )
    (net (code "78") (name "unconnected-(JP2-Pad4)") (class "Default")
      (node (ref "JP2") (pin "4") (pinfunction "4_4") (pintype "passive"))
    )
    (net (code "79") (name "unconnected-(JP2-Pad5)") (class "Default")
      (node (ref "JP2") (pin "5") (pinfunction "5_5") (pintype "passive"))
    )
    (net (code "80") (name "unconnected-(JP2-Pad6)") (class "Default")
      (node (ref "JP2") (pin "6") (pinfunction "6_6") (pintype "passive"))
    )
    (net (code "81") (name "unconnected-(JP2-Pad7)") (class "Default")
      (node (ref "JP2") (pin "7") (pinfunction "7_7") (pintype "passive"))
    )
    (net (code "82") (name "unconnected-(JP2-Pad8)") (class "Default")
      (node (ref "JP2") (pin "8") (pinfunction "8_8") (pintype "passive"))
    )
    (net (code "83") (name "unconnected-(JP2-Pad9)") (class "Default")
      (node (ref "JP2") (pin "9") (pinfunction "9_9") (pintype "passive"))
    )
    (net (code "84") (name "unconnected-(JP2-Pad10)") (class "Default")
      (node (ref "JP2") (pin "10") (pinfunction "10_10") (pintype "passive"))
    )
    (net (code "85") (name "unconnected-(JP2-Pad11)") (class "Default")
      (node (ref "JP2") (pin "11") (pinfunction "11_11") (pintype "passive"))
    )
    (net (code "86") (name "unconnected-(JP2-Pad12)") (class "Default")
      (node (ref "JP2") (pin "12") (pinfunction "12_12") (pintype "passive"))
    )
    (net (code "87") (name "unconnected-(JP2-Pad13)") (class "Default")
      (node (ref "JP2") (pin "13") (pinfunction "13_13") (pintype "passive"))
    )
    (net (code "88") (name "unconnected-(JP3-D+-PadD+1)") (class "Default")
      (node (ref "JP3") (pin "D+1") (pinfunction "D+_D+1") (pintype "bidirectional"))
    )
    (net (code "89") (name "unconnected-(JP3-D--PadD-1)") (class "Default")
      (node (ref "JP3") (pin "D-1") (pinfunction "D-_D-1") (pintype "bidirectional"))
    )
    (net (code "90") (name "unconnected-(JP203-Pad1)") (class "Default")
      (node (ref "JP203") (pin "1") (pinfunction "1_1") (pintype "passive"))
    )
    (net (code "91") (name "unconnected-(JP203-Pad2)") (class "Default")
      (node (ref "JP203") (pin "2") (pinfunction "2_2") (pintype "passive"))
    )
    (net (code "92") (name "unconnected-(JP203-Pad3)") (class "Default")
      (node (ref "JP203") (pin "3") (pinfunction "3_3") (pintype "passive"))
    )
    (net (code "93") (name "unconnected-(JP203-Pad4)") (class "Default")
      (node (ref "JP203") (pin "4") (pinfunction "4_4") (pintype "passive"))
    )
    (net (code "94") (name "unconnected-(JP203-Pad5)") (class "Default")
      (node (ref "JP203") (pin "5") (pinfunction "5_5") (pintype "passive"))
    )
    (net (code "95") (name "unconnected-(JP203-Pad6)") (class "Default")
      (node (ref "JP203") (pin "6") (pinfunction "6_6") (pintype "passive"))
    )
    (net (code "96") (name "unconnected-(JP203-Pad7)") (class "Default")
      (node (ref "JP203") (pin "7") (pinfunction "7_7") (pintype "passive"))
    )
    (net (code "97") (name "unconnected-(JP203-Pad8)") (class "Default")
      (node (ref "JP203") (pin "8") (pinfunction "8_8") (pintype "passive"))
    )
    (net (code "98") (name "unconnected-(JP203-Pad9)") (class "Default")
      (node (ref "JP203") (pin "9") (pinfunction "9_9") (pintype "passive"))
    )
    (net (code "99") (name "unconnected-(JP203-Pad10)") (class "Default")
      (node (ref "JP203") (pin "10") (pinfunction "10_10") (pintype "passive"))
    )
    (net (code "100") (name "unconnected-(JP203-Pad11)") (class "Default")
      (node (ref "JP203") (pin "11") (pinfunction "11_11") (pintype "passive"))
    )
    (net (code "101") (name "unconnected-(JP203-Pad12)") (class "Default")
      (node (ref "JP203") (pin "12") (pinfunction "12_12") (pintype "passive"))
    )
    (net (code "102") (name "unconnected-(JP203-Pad13)") (class "Default")
      (node (ref "JP203") (pin "13") (pinfunction "13_13") (pintype "passive"))
    )
    (net (code "103") (name "unconnected-(JP204-Pad3)") (class "Default")
      (node (ref "JP204") (pin "3") (pinfunction "3_3") (pintype "passive"))
    )
    (net (code "104") (name "unconnected-(JP204-Pad4)") (class "Default")
      (node (ref "JP204") (pin "4") (pinfunction "4_4") (pintype "passive"))
    )
    (net (code "105") (name "unconnected-(JP204-Pad5)") (class "Default")
      (node (ref "JP204") (pin "5") (pinfunction "5_5") (pintype "passive"))
    )
    (net (code "106") (name "unconnected-(JP204-Pad6)") (class "Default")
      (node (ref "JP204") (pin "6") (pinfunction "6_6") (pintype "passive"))
    )
    (net (code "107") (name "unconnected-(JP204-Pad7)") (class "Default")
      (node (ref "JP204") (pin "7") (pinfunction "7_7") (pintype "passive"))
    )
    (net (code "108") (name "unconnected-(JP204-Pad8)") (class "Default")
      (node (ref "JP204") (pin "8") (pinfunction "8_8") (pintype "passive"))
    )
    (net (code "109") (name "unconnected-(JP204-Pad9)") (class "Default")
      (node (ref "JP204") (pin "9") (pinfunction "9_9") (pintype "passive"))
    )
    (net (code "110") (name "unconnected-(JP204-Pad10)") (class "Default")
      (node (ref "JP204") (pin "10") (pinfunction "10_10") (pintype "passive"))
    )
    (net (code "111") (name "unconnected-(JP204-Pad11)") (class "Default")
      (node (ref "JP204") (pin "11") (pinfunction "11_11") (pintype "passive"))
    )
    (net (code "112") (name "unconnected-(JP204-Pad12)") (class "Default")
      (node (ref "JP204") (pin "12") (pinfunction "12_12") (pintype "passive"))
    )
    (net (code "113") (name "unconnected-(JP204-Pad13)") (class "Default")
      (node (ref "JP204") (pin "13") (pinfunction "13_13") (pintype "passive"))
    )
    (net (code "114") (name "unconnected-(JP205-Pad3)") (class "Default")
      (node (ref "JP205") (pin "3") (pinfunction "3_3") (pintype "passive"))
    )
    (net (code "115") (name "unconnected-(JP205-Pad4)") (class "Default")
      (node (ref "JP205") (pin "4") (pinfunction "4_4") (pintype "passive"))
    )
    (net (code "116") (name "unconnected-(JP205-Pad5)") (class "Default")
      (node (ref "JP205") (pin "5") (pinfunction "5_5") (pintype "passive"))
    )
    (net (code "117") (name "unconnected-(JP205-Pad6)") (class "Default")
      (node (ref "JP205") (pin "6") (pinfunction "6_6") (pintype "passive"))
    )
    (net (code "118") (name "unconnected-(JP205-Pad7)") (class "Default")
      (node (ref "JP205") (pin "7") (pinfunction "7_7") (pintype "passive"))
    )
    (net (code "119") (name "unconnected-(JP205-Pad8)") (class "Default")
      (node (ref "JP205") (pin "8") (pinfunction "8_8") (pintype "passive"))
    )
    (net (code "120") (name "unconnected-(JP205-Pad9)") (class "Default")
      (node (ref "JP205") (pin "9") (pinfunction "9_9") (pintype "passive"))
    )
    (net (code "121") (name "unconnected-(JP206-Pad3)") (class "Default")
      (node (ref "JP206") (pin "3") (pinfunction "3_3") (pintype "passive"))
    )
    (net (code "122") (name "unconnected-(JP206-Pad4)") (class "Default")
      (node (ref "JP206") (pin "4") (pinfunction "4_4") (pintype "passive"))
    )
    (net (code "123") (name "unconnected-(JP206-Pad5)") (class "Default")
      (node (ref "JP206") (pin "5") (pinfunction "5_5") (pintype "passive"))
    )
    (net (code "124") (name "unconnected-(JP206-Pad6)") (class "Default")
      (node (ref "JP206") (pin "6") (pinfunction "6_6") (pintype "passive"))
    )
    (net (code "125") (name "unconnected-(JP206-Pad7)") (class "Default")
      (node (ref "JP206") (pin "7") (pinfunction "7_7") (pintype "passive"))
    )
    (net (code "126") (name "unconnected-(JP206-Pad8)") (class "Default")
      (node (ref "JP206") (pin "8") (pinfunction "8_8") (pintype "passive"))
    )
    (net (code "127") (name "unconnected-(JP206-Pad9)") (class "Default")
      (node (ref "JP206") (pin "9") (pinfunction "9_9") (pintype "passive"))
    )
    (net (code "128") (name "unconnected-(JP207-Pad3)") (class "Default")
      (node (ref "JP207") (pin "3") (pinfunction "3_3") (pintype "passive"))
    )
    (net (code "129") (name "unconnected-(JP207-Pad4)") (class "Default")
      (node (ref "JP207") (pin "4") (pinfunction "4_4") (pintype "passive"))
    )
    (net (code "130") (name "unconnected-(JP207-Pad5)") (class "Default")
      (node (ref "JP207") (pin "5") (pinfunction "5_5") (pintype "passive"))
    )
    (net (code "131") (name "unconnected-(JP207-Pad6)") (class "Default")
      (node (ref "JP207") (pin "6") (pinfunction "6_6") (pintype "passive"))
    )
    (net (code "132") (name "unconnected-(JP207-Pad7)") (class "Default")
      (node (ref "JP207") (pin "7") (pinfunction "7_7") (pintype "passive"))
    )
    (net (code "133") (name "unconnected-(JP207-Pad8)") (class "Default")
      (node (ref "JP207") (pin "8") (pinfunction "8_8") (pintype "passive"))
    )
    (net (code "134") (name "unconnected-(JP207-Pad9)") (class "Default")
      (node (ref "JP207") (pin "9") (pinfunction "9_9") (pintype "passive"))
    )
    (net (code "135") (name "unconnected-(JP208-Pad3)") (class "Default")
      (node (ref "JP208") (pin "3") (pinfunction "3_3") (pintype "passive"))
    )
    (net (code "136") (name "unconnected-(JP208-Pad4)") (class "Default")
      (node (ref "JP208") (pin "4") (pinfunction "4_4") (pintype "passive"))
    )
    (net (code "137") (name "unconnected-(JP208-Pad5)") (class "Default")
      (node (ref "JP208") (pin "5") (pinfunction "5_5") (pintype "passive"))
    )
    (net (code "138") (name "unconnected-(JP208-Pad6)") (class "Default")
      (node (ref "JP208") (pin "6") (pinfunction "6_6") (pintype "passive"))
    )
    (net (code "139") (name "unconnected-(JP208-Pad7)") (class "Default")
      (node (ref "JP208") (pin "7") (pinfunction "7_7") (pintype "passive"))
    )
    (net (code "140") (name "unconnected-(JP208-Pad8)") (class "Default")
      (node (ref "JP208") (pin "8") (pinfunction "8_8") (pintype "passive"))
    )
    (net (code "141") (name "unconnected-(JP208-Pad9)") (class "Default")
      (node (ref "JP208") (pin "9") (pinfunction "9_9") (pintype "passive"))
    )
    (net (code "142") (name "unconnected-(JP209-Pad3)") (class "Default")
      (node (ref "JP209") (pin "3") (pinfunction "3_3") (pintype "passive"))
    )
    (net (code "143") (name "unconnected-(JP209-Pad4)") (class "Default")
      (node (ref "JP209") (pin "4") (pinfunction "4_4") (pintype "passive"))
    )
    (net (code "144") (name "unconnected-(JP209-Pad5)") (class "Default")
      (node (ref "JP209") (pin "5") (pinfunction "5_5") (pintype "passive"))
    )
    (net (code "145") (name "unconnected-(JP209-Pad6)") (class "Default")
      (node (ref "JP209") (pin "6") (pinfunction "6_6") (pintype "passive"))
    )
    (net (code "146") (name "unconnected-(JP209-Pad7)") (class "Default")
      (node (ref "JP209") (pin "7") (pinfunction "7_7") (pintype "passive"))
    )
    (net (code "147") (name "unconnected-(JP209-Pad8)") (class "Default")
      (node (ref "JP209") (pin "8") (pinfunction "8_8") (pintype "passive"))
    )
    (net (code "148") (name "unconnected-(JP209-Pad9)") (class "Default")
      (node (ref "JP209") (pin "9") (pinfunction "9_9") (pintype "passive"))
    )
    (net (code "149") (name "unconnected-(JP210-Pad3)") (class "Default")
      (node (ref "JP210") (pin "3") (pinfunction "3_3") (pintype "passive"))
    )
    (net (code "150") (name "unconnected-(JP210-Pad4)") (class "Default")
      (node (ref "JP210") (pin "4") (pinfunction "4_4") (pintype "passive"))
    )
    (net (code "151") (name "unconnected-(JP210-Pad5)") (class "Default")
      (node (ref "JP210") (pin "5") (pinfunction "5_5") (pintype "passive"))
    )
    (net (code "152") (name "unconnected-(JP210-Pad6)") (class "Default")
      (node (ref "JP210") (pin "6") (pinfunction "6_6") (pintype "passive"))
    )
    (net (code "153") (name "unconnected-(JP210-Pad7)") (class "Default")
      (node (ref "JP210") (pin "7") (pinfunction "7_7") (pintype "passive"))
    )
    (net (code "154") (name "unconnected-(JP210-Pad8)") (class "Default")
      (node (ref "JP210") (pin "8") (pinfunction "8_8") (pintype "passive"))
    )
    (net (code "155") (name "unconnected-(JP210-Pad9)") (class "Default")
      (node (ref "JP210") (pin "9") (pinfunction "9_9") (pintype "passive"))
    )
    (net (code "156") (name "unconnected-(JP211-Pad3)") (class "Default")
      (node (ref "JP211") (pin "3") (pinfunction "3_3") (pintype "passive"))
    )
    (net (code "157") (name "unconnected-(JP211-Pad4)") (class "Default")
      (node (ref "JP211") (pin "4") (pinfunction "4_4") (pintype "passive"))
    )
    (net (code "158") (name "unconnected-(JP211-Pad5)") (class "Default")
      (node (ref "JP211") (pin "5") (pinfunction "5_5") (pintype "passive"))
    )
    (net (code "159") (name "unconnected-(JP211-Pad6)") (class "Default")
      (node (ref "JP211") (pin "6") (pinfunction "6_6") (pintype "passive"))
    )
    (net (code "160") (name "unconnected-(JP211-Pad7)") (class "Default")
      (node (ref "JP211") (pin "7") (pinfunction "7_7") (pintype "passive"))
    )
    (net (code "161") (name "unconnected-(JP211-Pad8)") (class "Default")
      (node (ref "JP211") (pin "8") (pinfunction "8_8") (pintype "passive"))
    )
    (net (code "162") (name "unconnected-(JP211-Pad9)") (class "Default")
      (node (ref "JP211") (pin "9") (pinfunction "9_9") (pintype "passive"))
    )
    (net (code "163") (name "unconnected-(JP212-Pad3)") (class "Default")
      (node (ref "JP212") (pin "3") (pinfunction "3_3") (pintype "passive"))
    )
    (net (code "164") (name "unconnected-(JP212-Pad4)") (class "Default")
      (node (ref "JP212") (pin "4") (pinfunction "4_4") (pintype "passive"))
    )
    (net (code "165") (name "unconnected-(JP212-Pad5)") (class "Default")
      (node (ref "JP212") (pin "5") (pinfunction "5_5") (pintype "passive"))
    )
    (net (code "166") (name "unconnected-(JP212-Pad6)") (class "Default")
      (node (ref "JP212") (pin "6") (pinfunction "6_6") (pintype "passive"))
    )
    (net (code "167") (name "unconnected-(JP212-Pad7)") (class "Default")
      (node (ref "JP212") (pin "7") (pinfunction "7_7") (pintype "passive"))
    )
    (net (code "168") (name "unconnected-(JP212-Pad8)") (class "Default")
      (node (ref "JP212") (pin "8") (pinfunction "8_8") (pintype "passive"))
    )
    (net (code "169") (name "unconnected-(JP212-Pad9)") (class "Default")
      (node (ref "JP212") (pin "9") (pinfunction "9_9") (pintype "passive"))
    )
    (net (code "170") (name "unconnected-(JP213-Pad1)") (class "Default")
      (node (ref "JP213") (pin "1") (pinfunction "1_1") (pintype "passive"))
    )
    (net (code "171") (name "unconnected-(JP213-Pad2)") (class "Default")
      (node (ref "JP213") (pin "2") (pinfunction "2_2") (pintype "passive"))
    )
    (net (code "172") (name "unconnected-(JP213-Pad3)") (class "Default")
      (node (ref "JP213") (pin "3") (pinfunction "3_3") (pintype "passive"))
    )
    (net (code "173") (name "unconnected-(JP213-Pad4)") (class "Default")
      (node (ref "JP213") (pin "4") (pinfunction "4_4") (pintype "passive"))
    )
    (net (code "174") (name "unconnected-(JP213-Pad5)") (class "Default")
      (node (ref "JP213") (pin "5") (pinfunction "5_5") (pintype "passive"))
    )
    (net (code "175") (name "unconnected-(JP213-Pad6)") (class "Default")
      (node (ref "JP213") (pin "6") (pinfunction "6_6") (pintype "passive"))
    )
    (net (code "176") (name "unconnected-(JP213-Pad7)") (class "Default")
      (node (ref "JP213") (pin "7") (pinfunction "7_7") (pintype "passive"))
    )
    (net (code "177") (name "unconnected-(JP213-Pad8)") (class "Default")
      (node (ref "JP213") (pin "8") (pinfunction "8_8") (pintype "passive"))
    )
    (net (code "178") (name "unconnected-(JP213-Pad9)") (class "Default")
      (node (ref "JP213") (pin "9") (pinfunction "9_9") (pintype "passive"))
    )
    (net (code "179") (name "unconnected-(JP213-Pad10)") (class "Default")
      (node (ref "JP213") (pin "10") (pinfunction "10_10") (pintype "passive"))
    )
    (net (code "180") (name "unconnected-(JP213-Pad11)") (class "Default")
      (node (ref "JP213") (pin "11") (pinfunction "11_11") (pintype "passive"))
    )
    (net (code "181") (name "unconnected-(JP213-Pad12)") (class "Default")
      (node (ref "JP213") (pin "12") (pinfunction "12_12") (pintype "passive"))
    )
    (net (code "182") (name "unconnected-(JP213-Pad13)") (class "Default")
      (node (ref "JP213") (pin "13") (pinfunction "13_13") (pintype "passive"))
    )
    (net (code "183") (name "unconnected-(JP214-Pad1)") (class "Default")
      (node (ref "JP214") (pin "1") (pinfunction "1_1") (pintype "passive"))
    )
    (net (code "184") (name "unconnected-(JP214-Pad2)") (class "Default")
      (node (ref "JP214") (pin "2") (pinfunction "2_2") (pintype "passive"))
    )
    (net (code "185") (name "unconnected-(JP214-Pad3)") (class "Default")
      (node (ref "JP214") (pin "3") (pinfunction "3_3") (pintype "passive"))
    )
    (net (code "186") (name "unconnected-(JP214-Pad4)") (class "Default")
      (node (ref "JP214") (pin "4") (pinfunction "4_4") (pintype "passive"))
    )
    (net (code "187") (name "unconnected-(JP214-Pad5)") (class "Default")
      (node (ref "JP214") (pin "5") (pinfunction "5_5") (pintype "passive"))
    )
    (net (code "188") (name "unconnected-(JP214-Pad6)") (class "Default")
      (node (ref "JP214") (pin "6") (pinfunction "6_6") (pintype "passive"))
    )
    (net (code "189") (name "unconnected-(JP214-Pad7)") (class "Default")
      (node (ref "JP214") (pin "7") (pinfunction "7_7") (pintype "passive"))
    )
    (net (code "190") (name "unconnected-(JP214-Pad8)") (class "Default")
      (node (ref "JP214") (pin "8") (pinfunction "8_8") (pintype "passive"))
    )
    (net (code "191") (name "unconnected-(JP214-Pad9)") (class "Default")
      (node (ref "JP214") (pin "9") (pinfunction "9_9") (pintype "passive"))
    )
    (net (code "192") (name "unconnected-(JP214-Pad10)") (class "Default")
      (node (ref "JP214") (pin "10") (pinfunction "10_10") (pintype "passive"))
    )
    (net (code "193") (name "unconnected-(JP214-Pad11)") (class "Default")
      (node (ref "JP214") (pin "11") (pinfunction "11_11") (pintype "passive"))
    )
    (net (code "194") (name "unconnected-(JP214-Pad12)") (class "Default")
      (node (ref "JP214") (pin "12") (pinfunction "12_12") (pintype "passive"))
    )
    (net (code "195") (name "unconnected-(JP214-Pad13)") (class "Default")
      (node (ref "JP214") (pin "13") (pinfunction "13_13") (pintype "passive"))
    )
  )
)
